# hello.net
KiCad netlist of a schematic drawn in EAGLE
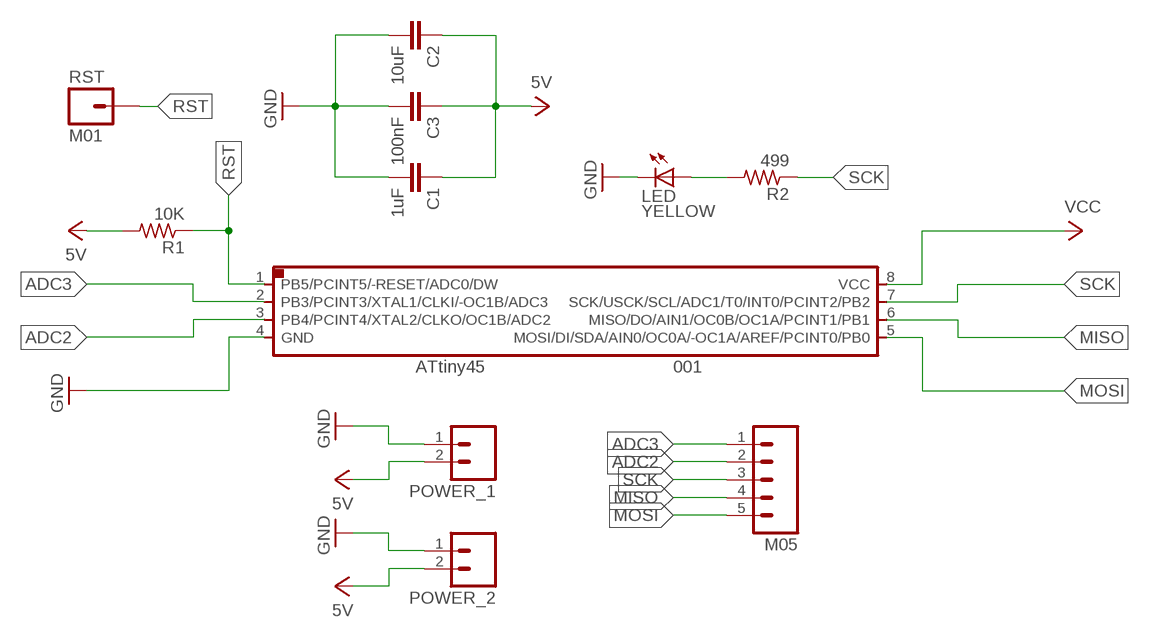
[diagram p0: schematic, sheet 1]

(export (version "E")
  (design (tool "Eeschema 10.0.6"))
  (components
    (comp (ref "001")
      (value "ATTINY45SI")
      (footprint "eagle-import:SOIC8")
      (libsource (lib "eagle-import") (part "ATTINY45SI"))
    )
    (comp (ref "C1")
      (value "1uF")
      (footprint "eagle-import:1206")
      (libsource (lib "eagle-import") (part "CAP1206"))
    )
    (comp (ref "C2")
      (value "10uF")
      (footprint "eagle-import:1206")
      (libsource (lib "eagle-import") (part "CAP1206"))
    )
    (comp (ref "C3")
      (value "100nF")
      (footprint "eagle-import:1206")
      (libsource (lib "eagle-import") (part "CAP1206"))
    )
    (comp (ref "LED")
      (value "YELLOW")
      (footprint "eagle-import:LED1206FAB")
      (libsource (lib "eagle-import") (part "LEDFAB1206"))
    )
    (comp (ref "M05")
      (value "M05")
      (footprint "eagle-import:05P")
      (libsource (lib "eagle-import") (part "M05"))
    )
    (comp (ref "POWER_1")
      (value "M02")
      (footprint "eagle-import:02P")
      (libsource (lib "eagle-import") (part "M02"))
    )
    (comp (ref "POWER_2")
      (value "M02")
      (footprint "eagle-import:02P")
      (libsource (lib "eagle-import") (part "M02"))
    )
    (comp (ref "R1")
      (value "10K")
      (footprint "eagle-import:R1206FAB")
      (libsource (lib "eagle-import") (part "RES-US1206FAB"))
    )
    (comp (ref "R2")
      (value "499")
      (footprint "eagle-import:R1206FAB")
      (libsource (lib "eagle-import") (part "fablab_RES-US1206FAB"))
    )
    (comp (ref "RST")
      (value "M01")
      (footprint "eagle-import:1X01_LONGPAD")
      (libsource (lib "eagle-import") (part "M01PTH_LONGPAD"))
    )
  )
  (nets
    (net (code "1") (name "5V") (class "Default")
      (node (ref "001") (pin "8") (pinfunction "VCC_8") (pintype "bidirectional"))
      (node (ref "C1") (pin "1") (pinfunction "1_1") (pintype "passive"))
      (node (ref "C2") (pin "1") (pinfunction "1_1") (pintype "passive"))
      (node (ref "C3") (pin "1") (pinfunction "1_1") (pintype "passive"))
      (node (ref "POWER_1") (pin "2") (pinfunction "2_2") (pintype "passive"))
      (node (ref "POWER_2") (pin "2") (pinfunction "2_2") (pintype "passive"))
      (node (ref "R1") (pin "2") (pinfunction "2_2") (pintype "passive"))
    )
    (net (code "2") (name "ADC2") (class "Default")
      (node (ref "001") (pin "3") (pinfunction "PB4/PCINT4/XTAL2/CLKO/OC1B/ADC2_3") (pintype "bidirectional"))
      (node (ref "M05") (pin "2") (pinfunction "2_2") (pintype "passive"))
    )
    (net (code "3") (name "ADC3") (class "Default")
      (node (ref "001") (pin "2") (pinfunction "PB3/PCINT3/XTAL1/CLKI/-OC1B/ADC3_2") (pintype "bidirectional"))
      (node (ref "M05") (pin "1") (pinfunction "1_1") (pintype "passive"))
    )
    (net (code "4") (name "GND") (class "Default")
      (node (ref "001") (pin "4") (pinfunction "GND_4") (pintype "bidirectional"))
      (node (ref "C1") (pin "2") (pinfunction "2_2") (pintype "passive"))
      (node (ref "C2") (pin "2") (pinfunction "2_2") (pintype "passive"))
      (node (ref "C3") (pin "2") (pinfunction "2_2") (pintype "passive"))
      (node (ref "LED") (pin "2") (pinfunction "C_2") (pintype "passive"))
      (node (ref "POWER_1") (pin "1") (pinfunction "1_1") (pintype "passive"))
      (node (ref "POWER_2") (pin "1") (pinfunction "1_1") (pintype "passive"))
    )
    (net (code "5") (name "MISO") (class "Default")
      (node (ref "001") (pin "6") (pinfunction "MISO/DO/AIN1/OC0B/OC1A/PCINT1/PB1_6") (pintype "bidirectional"))
      (node (ref "M05") (pin "4") (pinfunction "4_4") (pintype "passive"))
    )
    (net (code "6") (name "MOSI") (class "Default")
      (node (ref "001") (pin "5") (pinfunction "MOSI/DI/SDA/AIN0/OC0A/-OC1A/AREF/PCINT0/PB0_5") (pintype "bidirectional"))
      (node (ref "M05") (pin "5") (pinfunction "5_5") (pintype "passive"))
    )
    (net (code "7") (name "Net-(LED-A)") (class "Default")
      (node (ref "LED") (pin "1") (pinfunction "A_1") (pintype "passive"))
      (node (ref "R2") (pin "2") (pinfunction "2_2") (pintype "passive"))
    )
    (net (code "8") (name "RST") (class "Default")
      (node (ref "001") (pin "1") (pinfunction "PB5/PCINT5/-RESET/ADC0/DW_1") (pintype "bidirectional"))
      (node (ref "R1") (pin "1") (pinfunction "1_1") (pintype "passive"))
      (node (ref "RST") (pin "1") (pinfunction "1_1") (pintype "passive"))
    )
    (net (code "9") (name "SCK") (class "Default")
      (node (ref "001") (pin "7") (pinfunction "SCK/USCK/SCL/ADC1/T0/INT0/PCINT2/PB2_7") (pintype "bidirectional"))
      (node (ref "M05") (pin "3") (pinfunction "3_3") (pintype "passive"))
      (node (ref "R2") (pin "1") (pinfunction "1_1") (pintype "passive"))
    )
  )
)
